# SCH_Addressable_through_hole_LEDs_2022-0.net
KiCad netlist of a schematic drawn in EasyEDA
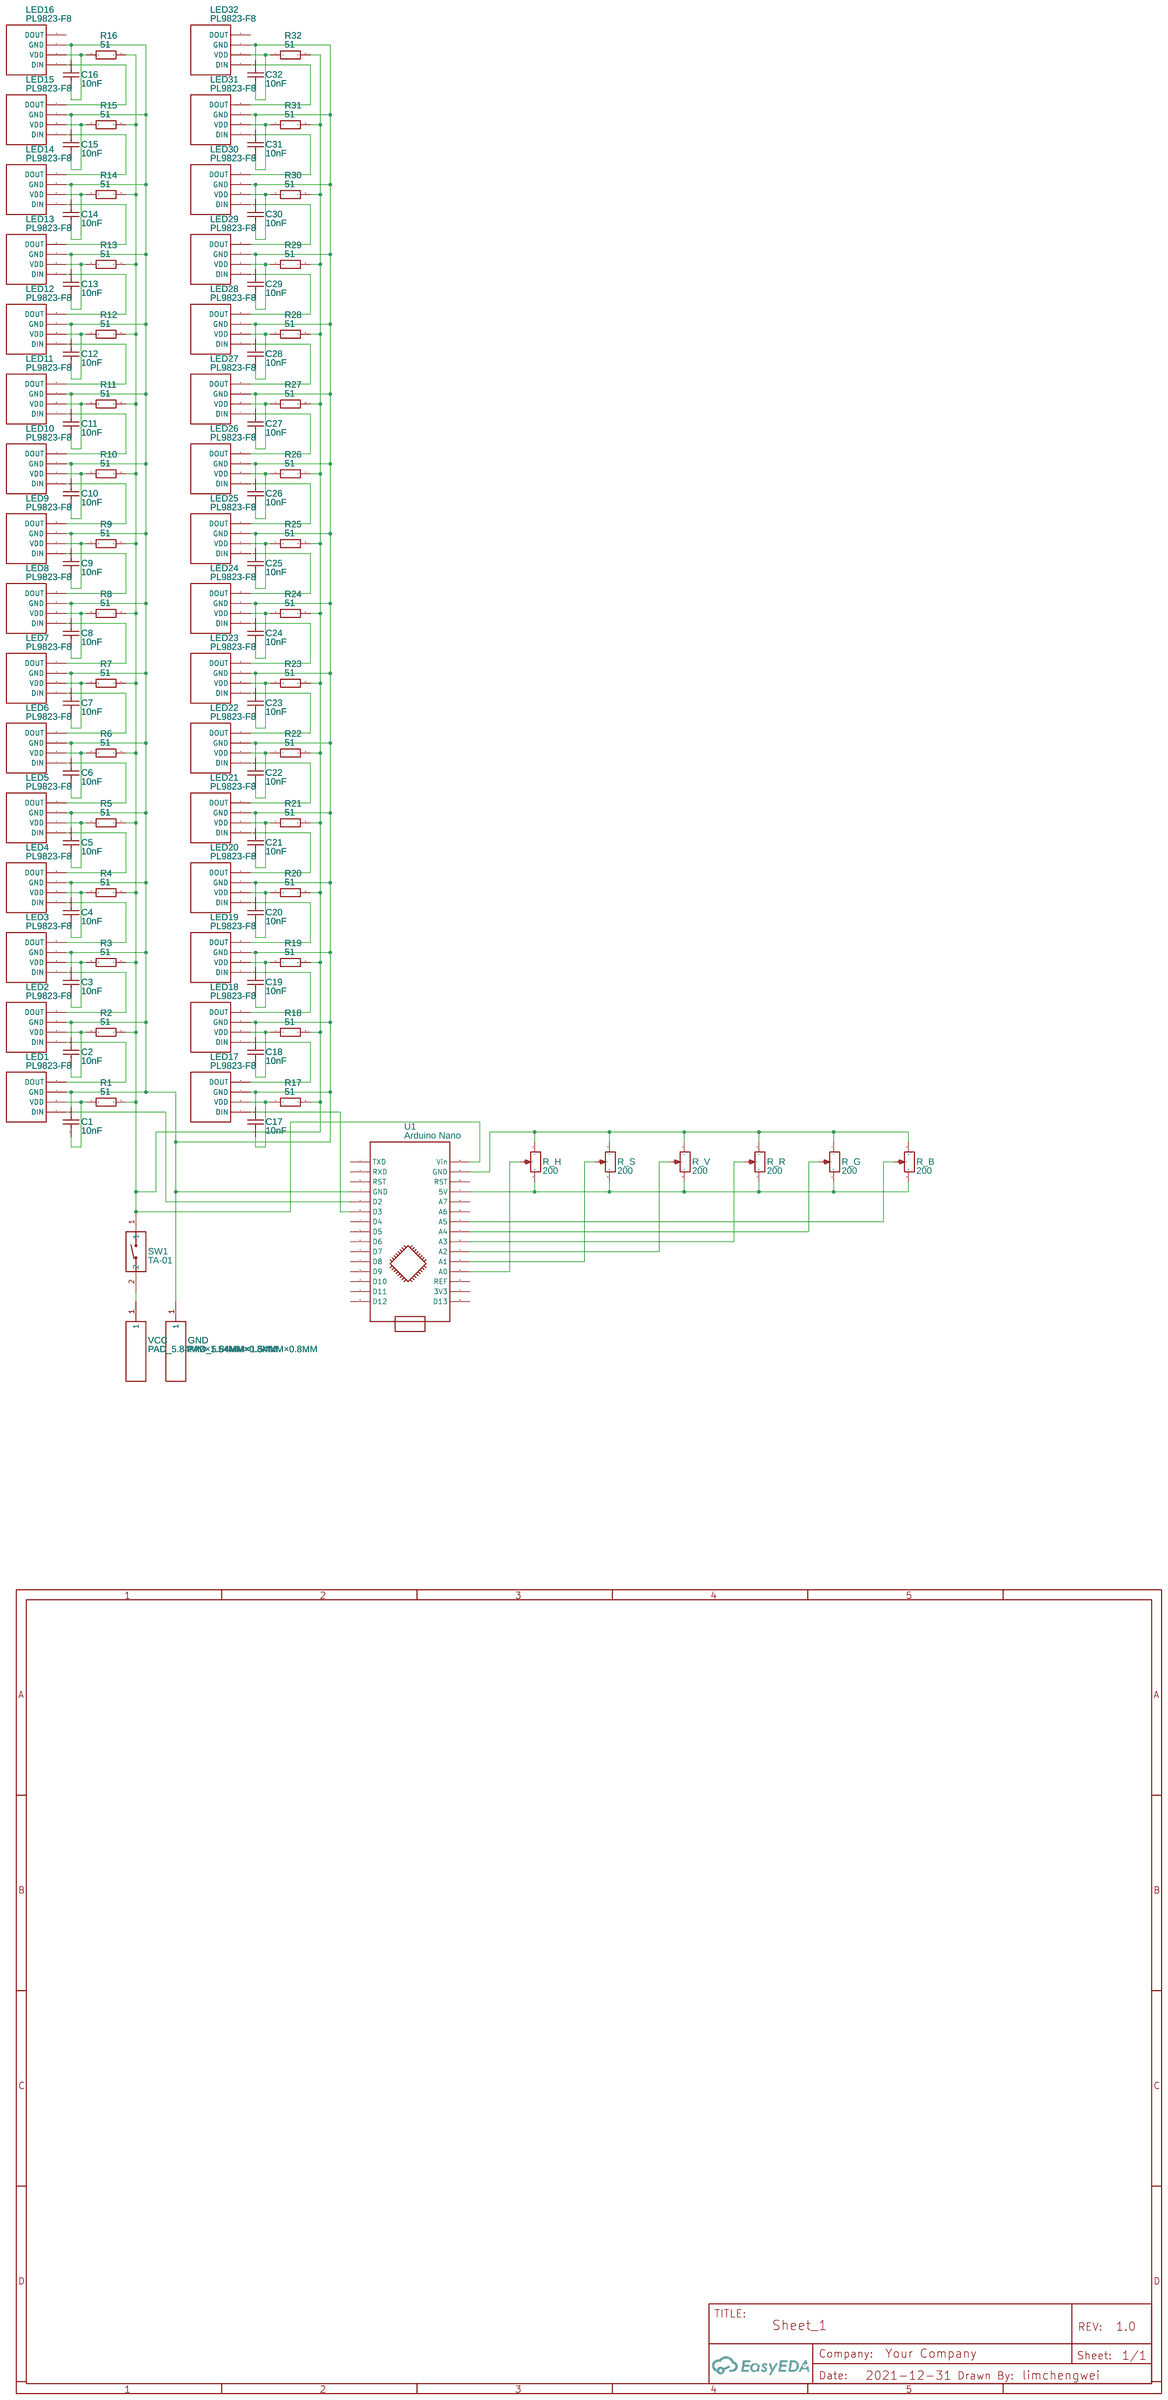
[diagram p0: schematic sheet]

(export (version "E")
  (design (tool "Eeschema 10.0.6"))
  (components
    (comp (ref "C1")
      (value "10nF")
      (fields
        (field (name "BOM_Manufacturer Part") "CC1H103ZC1FD3F4D10MF")
        (field (name "BOM_Supplier Part") "C254084")
      )
      (libsource (lib "") (part "CC1H103ZC1FD3F4D10MF"))
    )
    (comp (ref "C2")
      (value "10nF")
      (fields
        (field (name "BOM_Manufacturer Part") "CC1H103ZC1FD3F4D10MF")
        (field (name "BOM_Supplier Part") "C254084")
      )
      (libsource (lib "") (part "CC1H103ZC1FD3F4D10MF"))
    )
    (comp (ref "C3")
      (value "10nF")
      (fields
        (field (name "BOM_Manufacturer Part") "CC1H103ZC1FD3F4D10MF")
        (field (name "BOM_Supplier Part") "C254084")
      )
      (libsource (lib "") (part "CC1H103ZC1FD3F4D10MF"))
    )
    (comp (ref "C4")
      (value "10nF")
      (fields
        (field (name "BOM_Manufacturer Part") "CC1H103ZC1FD3F4D10MF")
        (field (name "BOM_Supplier Part") "C254084")
      )
      (libsource (lib "") (part "CC1H103ZC1FD3F4D10MF"))
    )
    (comp (ref "C5")
      (value "10nF")
      (fields
        (field (name "BOM_Manufacturer Part") "CC1H103ZC1FD3F4D10MF")
        (field (name "BOM_Supplier Part") "C254084")
      )
      (libsource (lib "") (part "CC1H103ZC1FD3F4D10MF"))
    )
    (comp (ref "C6")
      (value "10nF")
      (fields
        (field (name "BOM_Manufacturer Part") "CC1H103ZC1FD3F4D10MF")
        (field (name "BOM_Supplier Part") "C254084")
      )
      (libsource (lib "") (part "CC1H103ZC1FD3F4D10MF"))
    )
    (comp (ref "C7")
      (value "10nF")
      (fields
        (field (name "BOM_Manufacturer Part") "CC1H103ZC1FD3F4D10MF")
        (field (name "BOM_Supplier Part") "C254084")
      )
      (libsource (lib "") (part "CC1H103ZC1FD3F4D10MF"))
    )
    (comp (ref "C8")
      (value "10nF")
      (fields
        (field (name "BOM_Manufacturer Part") "CC1H103ZC1FD3F4D10MF")
        (field (name "BOM_Supplier Part") "C254084")
      )
      (libsource (lib "") (part "CC1H103ZC1FD3F4D10MF"))
    )
    (comp (ref "C9")
      (value "10nF")
      (fields
        (field (name "BOM_Manufacturer Part") "CC1H103ZC1FD3F4D10MF")
        (field (name "BOM_Supplier Part") "C254084")
      )
      (libsource (lib "") (part "CC1H103ZC1FD3F4D10MF"))
    )
    (comp (ref "C10")
      (value "10nF")
      (fields
        (field (name "BOM_Manufacturer Part") "CC1H103ZC1FD3F4D10MF")
        (field (name "BOM_Supplier Part") "C254084")
      )
      (libsource (lib "") (part "CC1H103ZC1FD3F4D10MF"))
    )
    (comp (ref "C11")
      (value "10nF")
      (fields
        (field (name "BOM_Manufacturer Part") "CC1H103ZC1FD3F4D10MF")
        (field (name "BOM_Supplier Part") "C254084")
      )
      (libsource (lib "") (part "CC1H103ZC1FD3F4D10MF"))
    )
    (comp (ref "C12")
      (value "10nF")
      (fields
        (field (name "BOM_Manufacturer Part") "CC1H103ZC1FD3F4D10MF")
        (field (name "BOM_Supplier Part") "C254084")
      )
      (libsource (lib "") (part "CC1H103ZC1FD3F4D10MF"))
    )
    (comp (ref "C13")
      (value "10nF")
      (fields
        (field (name "BOM_Manufacturer Part") "CC1H103ZC1FD3F4D10MF")
        (field (name "BOM_Supplier Part") "C254084")
      )
      (libsource (lib "") (part "CC1H103ZC1FD3F4D10MF"))
    )
    (comp (ref "C14")
      (value "10nF")
      (fields
        (field (name "BOM_Manufacturer Part") "CC1H103ZC1FD3F4D10MF")
        (field (name "BOM_Supplier Part") "C254084")
      )
      (libsource (lib "") (part "CC1H103ZC1FD3F4D10MF"))
    )
    (comp (ref "C15")
      (value "10nF")
      (fields
        (field (name "BOM_Manufacturer Part") "CC1H103ZC1FD3F4D10MF")
        (field (name "BOM_Supplier Part") "C254084")
      )
      (libsource (lib "") (part "CC1H103ZC1FD3F4D10MF"))
    )
    (comp (ref "C16")
      (value "10nF")
      (fields
        (field (name "BOM_Manufacturer Part") "CC1H103ZC1FD3F4D10MF")
        (field (name "BOM_Supplier Part") "C254084")
      )
      (libsource (lib "") (part "CC1H103ZC1FD3F4D10MF"))
    )
    (comp (ref "C17")
      (value "10nF")
      (fields
        (field (name "BOM_Manufacturer Part") "CC1H103ZC1FD3F4D10MF")
        (field (name "BOM_Supplier Part") "C254084")
      )
      (libsource (lib "") (part "CC1H103ZC1FD3F4D10MF"))
    )
    (comp (ref "C18")
      (value "10nF")
      (fields
        (field (name "BOM_Manufacturer Part") "CC1H103ZC1FD3F4D10MF")
        (field (name "BOM_Supplier Part") "C254084")
      )
      (libsource (lib "") (part "CC1H103ZC1FD3F4D10MF"))
    )
    (comp (ref "C19")
      (value "10nF")
      (fields
        (field (name "BOM_Manufacturer Part") "CC1H103ZC1FD3F4D10MF")
        (field (name "BOM_Supplier Part") "C254084")
      )
      (libsource (lib "") (part "CC1H103ZC1FD3F4D10MF"))
    )
    (comp (ref "C20")
      (value "10nF")
      (fields
        (field (name "BOM_Manufacturer Part") "CC1H103ZC1FD3F4D10MF")
        (field (name "BOM_Supplier Part") "C254084")
      )
      (libsource (lib "") (part "CC1H103ZC1FD3F4D10MF"))
    )
    (comp (ref "C21")
      (value "10nF")
      (fields
        (field (name "BOM_Manufacturer Part") "CC1H103ZC1FD3F4D10MF")
        (field (name "BOM_Supplier Part") "C254084")
      )
      (libsource (lib "") (part "CC1H103ZC1FD3F4D10MF"))
    )
    (comp (ref "C22")
      (value "10nF")
      (fields
        (field (name "BOM_Manufacturer Part") "CC1H103ZC1FD3F4D10MF")
        (field (name "BOM_Supplier Part") "C254084")
      )
      (libsource (lib "") (part "CC1H103ZC1FD3F4D10MF"))
    )
    (comp (ref "C23")
      (value "10nF")
      (fields
        (field (name "BOM_Manufacturer Part") "CC1H103ZC1FD3F4D10MF")
        (field (name "BOM_Supplier Part") "C254084")
      )
      (libsource (lib "") (part "CC1H103ZC1FD3F4D10MF"))
    )
    (comp (ref "C24")
      (value "10nF")
      (fields
        (field (name "BOM_Manufacturer Part") "CC1H103ZC1FD3F4D10MF")
        (field (name "BOM_Supplier Part") "C254084")
      )
      (libsource (lib "") (part "CC1H103ZC1FD3F4D10MF"))
    )
    (comp (ref "C25")
      (value "10nF")
      (fields
        (field (name "BOM_Manufacturer Part") "CC1H103ZC1FD3F4D10MF")
        (field (name "BOM_Supplier Part") "C254084")
      )
      (libsource (lib "") (part "CC1H103ZC1FD3F4D10MF"))
    )
    (comp (ref "C26")
      (value "10nF")
      (fields
        (field (name "BOM_Manufacturer Part") "CC1H103ZC1FD3F4D10MF")
        (field (name "BOM_Supplier Part") "C254084")
      )
      (libsource (lib "") (part "CC1H103ZC1FD3F4D10MF"))
    )
    (comp (ref "C27")
      (value "10nF")
      (fields
        (field (name "BOM_Manufacturer Part") "CC1H103ZC1FD3F4D10MF")
        (field (name "BOM_Supplier Part") "C254084")
      )
      (libsource (lib "") (part "CC1H103ZC1FD3F4D10MF"))
    )
    (comp (ref "C28")
      (value "10nF")
      (fields
        (field (name "BOM_Manufacturer Part") "CC1H103ZC1FD3F4D10MF")
        (field (name "BOM_Supplier Part") "C254084")
      )
      (libsource (lib "") (part "CC1H103ZC1FD3F4D10MF"))
    )
    (comp (ref "C29")
      (value "10nF")
      (fields
        (field (name "BOM_Manufacturer Part") "CC1H103ZC1FD3F4D10MF")
        (field (name "BOM_Supplier Part") "C254084")
      )
      (libsource (lib "") (part "CC1H103ZC1FD3F4D10MF"))
    )
    (comp (ref "C30")
      (value "10nF")
      (fields
        (field (name "BOM_Manufacturer Part") "CC1H103ZC1FD3F4D10MF")
        (field (name "BOM_Supplier Part") "C254084")
      )
      (libsource (lib "") (part "CC1H103ZC1FD3F4D10MF"))
    )
    (comp (ref "C31")
      (value "10nF")
      (fields
        (field (name "BOM_Manufacturer Part") "CC1H103ZC1FD3F4D10MF")
        (field (name "BOM_Supplier Part") "C254084")
      )
      (libsource (lib "") (part "CC1H103ZC1FD3F4D10MF"))
    )
    (comp (ref "C32")
      (value "10nF")
      (fields
        (field (name "BOM_Manufacturer Part") "CC1H103ZC1FD3F4D10MF")
        (field (name "BOM_Supplier Part") "C254084")
      )
      (libsource (lib "") (part "CC1H103ZC1FD3F4D10MF"))
    )
    (comp (ref "GND")
      (value "PAD_5.84MM×1.54MM×0.8MM")
      (fields
        (field (name "BOM_Manufacturer Part") "PAD_5.84mm×1.54mm×0.8mm")
        (field (name "BOM_Supplier Part") "C9900000335")
      )
      (libsource (lib "") (part "PAD_5.84MM×1.54MM×0.8MM"))
    )
    (comp (ref "LED1")
      (value "PL9823-F8")
      (fields (field (name "BOM_Manufacturer Part") "PL9823"))
      (libsource (lib "") (part "PL9823-F8"))
    )
    (comp (ref "LED2")
      (value "PL9823-F8")
      (fields (field (name "BOM_Manufacturer Part") "PL9823"))
      (libsource (lib "") (part "PL9823-F8"))
    )
    (comp (ref "LED3")
      (value "PL9823-F8")
      (fields (field (name "BOM_Manufacturer Part") "PL9823"))
      (libsource (lib "") (part "PL9823-F8"))
    )
    (comp (ref "LED4")
      (value "PL9823-F8")
      (fields (field (name "BOM_Manufacturer Part") "PL9823"))
      (libsource (lib "") (part "PL9823-F8"))
    )
    (comp (ref "LED5")
      (value "PL9823-F8")
      (fields (field (name "BOM_Manufacturer Part") "PL9823"))
      (libsource (lib "") (part "PL9823-F8"))
    )
    (comp (ref "LED6")
      (value "PL9823-F8")
      (fields (field (name "BOM_Manufacturer Part") "PL9823"))
      (libsource (lib "") (part "PL9823-F8"))
    )
    (comp (ref "LED7")
      (value "PL9823-F8")
      (fields (field (name "BOM_Manufacturer Part") "PL9823"))
      (libsource (lib "") (part "PL9823-F8"))
    )
    (comp (ref "LED8")
      (value "PL9823-F8")
      (fields (field (name "BOM_Manufacturer Part") "PL9823"))
      (libsource (lib "") (part "PL9823-F8"))
    )
    (comp (ref "LED9")
      (value "PL9823-F8")
      (fields (field (name "BOM_Manufacturer Part") "PL9823"))
      (libsource (lib "") (part "PL9823-F8"))
    )
    (comp (ref "LED10")
      (value "PL9823-F8")
      (fields (field (name "BOM_Manufacturer Part") "PL9823"))
      (libsource (lib "") (part "PL9823-F8"))
    )
    (comp (ref "LED11")
      (value "PL9823-F8")
      (fields (field (name "BOM_Manufacturer Part") "PL9823"))
      (libsource (lib "") (part "PL9823-F8"))
    )
    (comp (ref "LED12")
      (value "PL9823-F8")
      (fields (field (name "BOM_Manufacturer Part") "PL9823"))
      (libsource (lib "") (part "PL9823-F8"))
    )
    (comp (ref "LED13")
      (value "PL9823-F8")
      (fields (field (name "BOM_Manufacturer Part") "PL9823"))
      (libsource (lib "") (part "PL9823-F8"))
    )
    (comp (ref "LED14")
      (value "PL9823-F8")
      (fields (field (name "BOM_Manufacturer Part") "PL9823"))
      (libsource (lib "") (part "PL9823-F8"))
    )
    (comp (ref "LED15")
      (value "PL9823-F8")
      (fields (field (name "BOM_Manufacturer Part") "PL9823"))
      (libsource (lib "") (part "PL9823-F8"))
    )
    (comp (ref "LED16")
      (value "PL9823-F8")
      (fields (field (name "BOM_Manufacturer Part") "PL9823"))
      (libsource (lib "") (part "PL9823-F8"))
    )
    (comp (ref "LED17")
      (value "PL9823-F8")
      (fields (field (name "BOM_Manufacturer Part") "PL9823"))
      (libsource (lib "") (part "PL9823-F8"))
    )
    (comp (ref "LED18")
      (value "PL9823-F8")
      (fields (field (name "BOM_Manufacturer Part") "PL9823"))
      (libsource (lib "") (part "PL9823-F8"))
    )
    (comp (ref "LED19")
      (value "PL9823-F8")
      (fields (field (name "BOM_Manufacturer Part") "PL9823"))
      (libsource (lib "") (part "PL9823-F8"))
    )
    (comp (ref "LED20")
      (value "PL9823-F8")
      (fields (field (name "BOM_Manufacturer Part") "PL9823"))
      (libsource (lib "") (part "PL9823-F8"))
    )
    (comp (ref "LED21")
      (value "PL9823-F8")
      (fields (field (name "BOM_Manufacturer Part") "PL9823"))
      (libsource (lib "") (part "PL9823-F8"))
    )
    (comp (ref "LED22")
      (value "PL9823-F8")
      (fields (field (name "BOM_Manufacturer Part") "PL9823"))
      (libsource (lib "") (part "PL9823-F8"))
    )
    (comp (ref "LED23")
      (value "PL9823-F8")
      (fields (field (name "BOM_Manufacturer Part") "PL9823"))
      (libsource (lib "") (part "PL9823-F8"))
    )
    (comp (ref "LED24")
      (value "PL9823-F8")
      (fields (field (name "BOM_Manufacturer Part") "PL9823"))
      (libsource (lib "") (part "PL9823-F8"))
    )
    (comp (ref "LED25")
      (value "PL9823-F8")
      (fields (field (name "BOM_Manufacturer Part") "PL9823"))
      (libsource (lib "") (part "PL9823-F8"))
    )
    (comp (ref "LED26")
      (value "PL9823-F8")
      (fields (field (name "BOM_Manufacturer Part") "PL9823"))
      (libsource (lib "") (part "PL9823-F8"))
    )
    (comp (ref "LED27")
      (value "PL9823-F8")
      (fields (field (name "BOM_Manufacturer Part") "PL9823"))
      (libsource (lib "") (part "PL9823-F8"))
    )
    (comp (ref "LED28")
      (value "PL9823-F8")
      (fields (field (name "BOM_Manufacturer Part") "PL9823"))
      (libsource (lib "") (part "PL9823-F8"))
    )
    (comp (ref "LED29")
      (value "PL9823-F8")
      (fields (field (name "BOM_Manufacturer Part") "PL9823"))
      (libsource (lib "") (part "PL9823-F8"))
    )
    (comp (ref "LED30")
      (value "PL9823-F8")
      (fields (field (name "BOM_Manufacturer Part") "PL9823"))
      (libsource (lib "") (part "PL9823-F8"))
    )
    (comp (ref "LED31")
      (value "PL9823-F8")
      (fields (field (name "BOM_Manufacturer Part") "PL9823"))
      (libsource (lib "") (part "PL9823-F8"))
    )
    (comp (ref "LED32")
      (value "PL9823-F8")
      (fields (field (name "BOM_Manufacturer Part") "PL9823"))
      (libsource (lib "") (part "PL9823-F8"))
    )
    (comp (ref "R1")
      (value "51")
      (fields (field (name "BOM_Supplier Part") "C119319"))
      (libsource (lib "") (part "MF1/4W-620Ω±1% T52"))
    )
    (comp (ref "R2")
      (value "51")
      (fields (field (name "BOM_Supplier Part") "C119319"))
      (libsource (lib "") (part "MF1/4W-620Ω±1% T52"))
    )
    (comp (ref "R3")
      (value "51")
      (fields (field (name "BOM_Supplier Part") "C119319"))
      (libsource (lib "") (part "MF1/4W-620Ω±1% T52"))
    )
    (comp (ref "R4")
      (value "51")
      (fields (field (name "BOM_Supplier Part") "C119319"))
      (libsource (lib "") (part "MF1/4W-620Ω±1% T52"))
    )
    (comp (ref "R5")
      (value "51")
      (fields (field (name "BOM_Supplier Part") "C119319"))
      (libsource (lib "") (part "MF1/4W-620Ω±1% T52"))
    )
    (comp (ref "R6")
      (value "51")
      (fields (field (name "BOM_Supplier Part") "C119319"))
      (libsource (lib "") (part "MF1/4W-620Ω±1% T52"))
    )
    (comp (ref "R7")
      (value "51")
      (fields (field (name "BOM_Supplier Part") "C119319"))
      (libsource (lib "") (part "MF1/4W-620Ω±1% T52"))
    )
    (comp (ref "R8")
      (value "51")
      (fields (field (name "BOM_Supplier Part") "C119319"))
      (libsource (lib "") (part "MF1/4W-620Ω±1% T52"))
    )
    (comp (ref "R9")
      (value "51")
      (fields (field (name "BOM_Supplier Part") "C119319"))
      (libsource (lib "") (part "MF1/4W-620Ω±1% T52"))
    )
    (comp (ref "R10")
      (value "51")
      (fields (field (name "BOM_Supplier Part") "C119319"))
      (libsource (lib "") (part "MF1/4W-620Ω±1% T52"))
    )
    (comp (ref "R11")
      (value "51")
      (fields (field (name "BOM_Supplier Part") "C119319"))
      (libsource (lib "") (part "MF1/4W-620Ω±1% T52"))
    )
    (comp (ref "R12")
      (value "51")
      (fields (field (name "BOM_Supplier Part") "C119319"))
      (libsource (lib "") (part "MF1/4W-620Ω±1% T52"))
    )
    (comp (ref "R13")
      (value "51")
      (fields (field (name "BOM_Supplier Part") "C119319"))
      (libsource (lib "") (part "MF1/4W-620Ω±1% T52"))
    )
    (comp (ref "R14")
      (value "51")
      (fields (field (name "BOM_Supplier Part") "C119319"))
      (libsource (lib "") (part "MF1/4W-620Ω±1% T52"))
    )
    (comp (ref "R15")
      (value "51")
      (fields (field (name "BOM_Supplier Part") "C119319"))
      (libsource (lib "") (part "MF1/4W-620Ω±1% T52"))
    )
    (comp (ref "R16")
      (value "51")
      (fields (field (name "BOM_Supplier Part") "C119319"))
      (libsource (lib "") (part "MF1/4W-620Ω±1% T52"))
    )
    (comp (ref "R17")
      (value "51")
      (fields (field (name "BOM_Supplier Part") "C119319"))
      (libsource (lib "") (part "MF1/4W-620Ω±1% T52"))
    )
    (comp (ref "R18")
      (value "51")
      (fields (field (name "BOM_Supplier Part") "C119319"))
      (libsource (lib "") (part "MF1/4W-620Ω±1% T52"))
    )
    (comp (ref "R19")
      (value "51")
      (fields (field (name "BOM_Supplier Part") "C119319"))
      (libsource (lib "") (part "MF1/4W-620Ω±1% T52"))
    )
    (comp (ref "R20")
      (value "51")
      (fields (field (name "BOM_Supplier Part") "C119319"))
      (libsource (lib "") (part "MF1/4W-620Ω±1% T52"))
    )
    (comp (ref "R21")
      (value "51")
      (fields (field (name "BOM_Supplier Part") "C119319"))
      (libsource (lib "") (part "MF1/4W-620Ω±1% T52"))
    )
    (comp (ref "R22")
      (value "51")
      (fields (field (name "BOM_Supplier Part") "C119319"))
      (libsource (lib "") (part "MF1/4W-620Ω±1% T52"))
    )
    (comp (ref "R23")
      (value "51")
      (fields (field (name "BOM_Supplier Part") "C119319"))
      (libsource (lib "") (part "MF1/4W-620Ω±1% T52"))
    )
    (comp (ref "R24")
      (value "51")
      (fields (field (name "BOM_Supplier Part") "C119319"))
      (libsource (lib "") (part "MF1/4W-620Ω±1% T52"))
    )
    (comp (ref "R25")
      (value "51")
      (fields (field (name "BOM_Supplier Part") "C119319"))
      (libsource (lib "") (part "MF1/4W-620Ω±1% T52"))
    )
    (comp (ref "R26")
      (value "51")
      (fields (field (name "BOM_Supplier Part") "C119319"))
      (libsource (lib "") (part "MF1/4W-620Ω±1% T52"))
    )
    (comp (ref "R27")
      (value "51")
      (fields (field (name "BOM_Supplier Part") "C119319"))
      (libsource (lib "") (part "MF1/4W-620Ω±1% T52"))
    )
    (comp (ref "R28")
      (value "51")
      (fields (field (name "BOM_Supplier Part") "C119319"))
      (libsource (lib "") (part "MF1/4W-620Ω±1% T52"))
    )
    (comp (ref "R29")
      (value "51")
      (fields (field (name "BOM_Supplier Part") "C119319"))
      (libsource (lib "") (part "MF1/4W-620Ω±1% T52"))
    )
    (comp (ref "R30")
      (value "51")
      (fields (field (name "BOM_Supplier Part") "C119319"))
      (libsource (lib "") (part "MF1/4W-620Ω±1% T52"))
    )
    (comp (ref "R31")
      (value "51")
      (fields (field (name "BOM_Supplier Part") "C119319"))
      (libsource (lib "") (part "MF1/4W-620Ω±1% T52"))
    )
    (comp (ref "R32")
      (value "51")
      (fields (field (name "BOM_Supplier Part") "C119319"))
      (libsource (lib "") (part "MF1/4W-620Ω±1% T52"))
    )
    (comp (ref "R_B")
      (value "200")
      (fields
        (field (name "BOM_Manufacturer Part") "3362P-1-201LF")
        (field (name "BOM_Supplier Part") "C124581")
      )
      (libsource (lib "") (part "3362P-1-201LF_4"))
    )
    (comp (ref "R_G")
      (value "200")
      (fields
        (field (name "BOM_Manufacturer Part") "3362P-1-201LF")
        (field (name "BOM_Supplier Part") "C124581")
      )
      (libsource (lib "") (part "3362P-1-201LF_5"))
    )
    (comp (ref "R_H")
      (value "200")
      (fields
        (field (name "BOM_Manufacturer Part") "3362P-1-201LF")
        (field (name "BOM_Supplier Part") "C124581")
      )
      (libsource (lib "") (part "3362P-1-201LF_1"))
    )
    (comp (ref "R_R")
      (value "200")
      (fields
        (field (name "BOM_Manufacturer Part") "3362P-1-201LF")
        (field (name "BOM_Supplier Part") "C124581")
      )
      (libsource (lib "") (part "3362P-1-201LF"))
    )
    (comp (ref "R_S")
      (value "200")
      (fields
        (field (name "BOM_Manufacturer Part") "3362P-1-201LF")
        (field (name "BOM_Supplier Part") "C124581")
      )
      (libsource (lib "") (part "3362P-1-201LF_3"))
    )
    (comp (ref "R_V")
      (value "200")
      (fields
        (field (name "BOM_Manufacturer Part") "3362P-1-201LF")
        (field (name "BOM_Supplier Part") "C124581")
      )
      (libsource (lib "") (part "3362P-1-201LF_2"))
    )
    (comp (ref "SW1")
      (value "TA-01")
      (fields (field (name "BOM_Supplier Part") "C559136"))
      (libsource (lib "") (part "TA-01"))
    )
    (comp (ref "U1") (value "Arduino Nano") (libsource (lib "") (part "Arduino Nano")))
    (comp (ref "VCC")
      (value "PAD_5.84MM×1.54MM×0.8MM")
      (fields
        (field (name "BOM_Manufacturer Part") "PAD_5.84mm×1.54mm×0.8mm")
        (field (name "BOM_Supplier Part") "C9900000335")
      )
      (libsource (lib "") (part "PAD_5.84MM×1.54MM×0.8MM_1"))
    )
  )
  (nets
    (net (code "1") (name "Net-(LED1-DIN)") (class "Default")
      (node (ref "LED1") (pin "4") (pinfunction "DIN_4") (pintype "unspecified"))
      (node (ref "U1") (pin "5") (pinfunction "D2_5") (pintype "unspecified"))
    )
    (net (code "2") (name "Net-(LED1-DOUT)") (class "Default")
      (node (ref "LED1") (pin "2") (pinfunction "DOUT_2") (pintype "unspecified"))
      (node (ref "LED2") (pin "4") (pinfunction "DIN_4") (pintype "unspecified"))
    )
    (net (code "3") (name "Net-(LED1-GND)") (class "Default")
      (node (ref "C1") (pin "2") (pinfunction "2_2") (pintype "input"))
      (node (ref "C10") (pin "2") (pinfunction "2_2") (pintype "input"))
      (node (ref "C11") (pin "2") (pinfunction "2_2") (pintype "input"))
      (node (ref "C12") (pin "2") (pinfunction "2_2") (pintype "input"))
      (node (ref "C13") (pin "2") (pinfunction "2_2") (pintype "input"))
      (node (ref "C14") (pin "2") (pinfunction "2_2") (pintype "input"))
      (node (ref "C15") (pin "2") (pinfunction "2_2") (pintype "input"))
      (node (ref "C16") (pin "2") (pinfunction "2_2") (pintype "input"))
      (node (ref "C17") (pin "2") (pinfunction "2_2") (pintype "input"))
      (node (ref "C18") (pin "2") (pinfunction "2_2") (pintype "input"))
      (node (ref "C19") (pin "2") (pinfunction "2_2") (pintype "input"))
      (node (ref "C2") (pin "2") (pinfunction "2_2") (pintype "input"))
      (node (ref "C20") (pin "2") (pinfunction "2_2") (pintype "input"))
      (node (ref "C21") (pin "2") (pinfunction "2_2") (pintype "input"))
      (node (ref "C22") (pin "2") (pinfunction "2_2") (pintype "input"))
      (node (ref "C23") (pin "2") (pinfunction "2_2") (pintype "input"))
      (node (ref "C24") (pin "2") (pinfunction "2_2") (pintype "input"))
      (node (ref "C25") (pin "2") (pinfunction "2_2") (pintype "input"))
      (node (ref "C26") (pin "2") (pinfunction "2_2") (pintype "input"))
      (node (ref "C27") (pin "2") (pinfunction "2_2") (pintype "input"))
      (node (ref "C28") (pin "2") (pinfunction "2_2") (pintype "input"))
      (node (ref "C29") (pin "2") (pinfunction "2_2") (pintype "input"))
      (node (ref "C3") (pin "2") (pinfunction "2_2") (pintype "input"))
      (node (ref "C30") (pin "2") (pinfunction "2_2") (pintype "input"))
      (node (ref "C31") (pin "2") (pinfunction "2_2") (pintype "input"))
      (node (ref "C32") (pin "2") (pinfunction "2_2") (pintype "input"))
      (node (ref "C4") (pin "2") (pinfunction "2_2") (pintype "input"))
      (node (ref "C5") (pin "2") (pinfunction "2_2") (pintype "input"))
      (node (ref "C6") (pin "2") (pinfunction "2_2") (pintype "input"))
      (node (ref "C7") (pin "2") (pinfunction "2_2") (pintype "input"))
      (node (ref "C8") (pin "2") (pinfunction "2_2") (pintype "input"))
      (node (ref "C9") (pin "2") (pinfunction "2_2") (pintype "input"))
      (node (ref "GND") (pin "1") (pinfunction "1_1") (pintype "unspecified"))
      (node (ref "LED1") (pin "1") (pinfunction "GND_1") (pintype "unspecified"))
      (node (ref "LED10") (pin "1") (pinfunction "GND_1") (pintype "unspecified"))
      (node (ref "LED11") (pin "1") (pinfunction "GND_1") (pintype "unspecified"))
      (node (ref "LED12") (pin "1") (pinfunction "GND_1") (pintype "unspecified"))
      (node (ref "LED13") (pin "1") (pinfunction "GND_1") (pintype "unspecified"))
      (node (ref "LED14") (pin "1") (pinfunction "GND_1") (pintype "unspecified"))
      (node (ref "LED15") (pin "1") (pinfunction "GND_1") (pintype "unspecified"))
      (node (ref "LED16") (pin "1") (pinfunction "GND_1") (pintype "unspecified"))
      (node (ref "LED17") (pin "1") (pinfunction "GND_1") (pintype "unspecified"))
      (node (ref "LED18") (pin "1") (pinfunction "GND_1") (pintype "unspecified"))
      (node (ref "LED19") (pin "1") (pinfunction "GND_1") (pintype "unspecified"))
      (node (ref "LED2") (pin "1") (pinfunction "GND_1") (pintype "unspecified"))
      (node (ref "LED20") (pin "1") (pinfunction "GND_1") (pintype "unspecified"))
      (node (ref "LED21") (pin "1") (pinfunction "GND_1") (pintype "unspecified"))
      (node (ref "LED22") (pin "1") (pinfunction "GND_1") (pintype "unspecified"))
      (node (ref "LED23") (pin "1") (pinfunction "GND_1") (pintype "unspecified"))
      (node (ref "LED24") (pin "1") (pinfunction "GND_1") (pintype "unspecified"))
      (node (ref "LED25") (pin "1") (pinfunction "GND_1") (pintype "unspecified"))
      (node (ref "LED26") (pin "1") (pinfunction "GND_1") (pintype "unspecified"))
      (node (ref "LED27") (pin "1") (pinfunction "GND_1") (pintype "unspecified"))
      (node (ref "LED28") (pin "1") (pinfunction "GND_1") (pintype "unspecified"))
      (node (ref "LED29") (pin "1") (pinfunction "GND_1") (pintype "unspecified"))
      (node (ref "LED3") (pin "1") (pinfunction "GND_1") (pintype "unspecified"))
      (node (ref "LED30") (pin "1") (pinfunction "GND_1") (pintype "unspecified"))
      (node (ref "LED31") (pin "1") (pinfunction "GND_1") (pintype "unspecified"))
      (node (ref "LED32") (pin "1") (pinfunction "GND_1") (pintype "unspecified"))
      (node (ref "LED4") (pin "1") (pinfunction "GND_1") (pintype "unspecified"))
      (node (ref "LED5") (pin "1") (pinfunction "GND_1") (pintype "unspecified"))
      (node (ref "LED6") (pin "1") (pinfunction "GND_1") (pintype "unspecified"))
      (node (ref "LED7") (pin "1") (pinfunction "GND_1") (pintype "unspecified"))
      (node (ref "LED8") (pin "1") (pinfunction "GND_1") (pintype "unspecified"))
      (node (ref "LED9") (pin "1") (pinfunction "GND_1") (pintype "unspecified"))
      (node (ref "U1") (pin "4") (pinfunction "GND_4") (pintype "unspecified"))
    )
    (net (code "4") (name "Net-(LED1-VDD)") (class "Default")
      (node (ref "C1") (pin "1") (pinfunction "1_1") (pintype "input"))
      (node (ref "LED1") (pin "3") (pinfunction "VDD_3") (pintype "unspecified"))
      (node (ref "R1") (pin "1") (pinfunction "1_1") (pintype "unspecified"))
    )
    (net (code "5") (name "Net-(LED2-DOUT)") (class "Default")
      (node (ref "LED2") (pin "2") (pinfunction "DOUT_2") (pintype "unspecified"))
      (node (ref "LED3") (pin "4") (pinfunction "DIN_4") (pintype "unspecified"))
    )
    (net (code "6") (name "Net-(LED2-VDD)") (class "Default")
      (node (ref "C2") (pin "1") (pinfunction "1_1") (pintype "input"))
      (node (ref "LED2") (pin "3") (pinfunction "VDD_3") (pintype "unspecified"))
      (node (ref "R2") (pin "1") (pinfunction "1_1") (pintype "unspecified"))
    )
    (net (code "7") (name "Net-(LED3-DOUT)") (class "Default")
      (node (ref "LED3") (pin "2") (pinfunction "DOUT_2") (pintype "unspecified"))
      (node (ref "LED4") (pin "4") (pinfunction "DIN_4") (pintype "unspecified"))
    )
    (net (code "8") (name "Net-(LED3-VDD)") (class "Default")
      (node (ref "C3") (pin "1") (pinfunction "1_1") (pintype "input"))
      (node (ref "LED3") (pin "3") (pinfunction "VDD_3") (pintype "unspecified"))
      (node (ref "R3") (pin "1") (pinfunction "1_1") (pintype "unspecified"))
    )
    (net (code "9") (name "Net-(LED4-DOUT)") (class "Default")
      (node (ref "LED4") (pin "2") (pinfunction "DOUT_2") (pintype "unspecified"))
      (node (ref "LED5") (pin "4") (pinfunction "DIN_4") (pintype "unspecified"))
    )
    (net (code "10") (name "Net-(LED4-VDD)") (class "Default")
      (node (ref "C4") (pin "1") (pinfunction "1_1") (pintype "input"))
      (node (ref "LED4") (pin "3") (pinfunction "VDD_3") (pintype "unspecified"))
      (node (ref "R4") (pin "1") (pinfunction "1_1") (pintype "unspecified"))
    )
    (net (code "11") (name "Net-(LED5-DOUT)") (class "Default")
      (node (ref "LED5") (pin "2") (pinfunction "DOUT_2") (pintype "unspecified"))
      (node (ref "LED6") (pin "4") (pinfunction "DIN_4") (pintype "unspecified"))
    )
    (net (code "12") (name "Net-(LED5-VDD)") (class "Default")
      (node (ref "C5") (pin "1") (pinfunction "1_1") (pintype "input"))
      (node (ref "LED5") (pin "3") (pinfunction "VDD_3") (pintype "unspecified"))
      (node (ref "R5") (pin "1") (pinfunction "1_1") (pintype "unspecified"))
    )
    (net (code "13") (name "Net-(LED6-DOUT)") (class "Default")
      (node (ref "LED6") (pin "2") (pinfunction "DOUT_2") (pintype "unspecified"))
      (node (ref "LED7") (pin "4") (pinfunction "DIN_4") (pintype "unspecified"))
    )
    (net (code "14") (name "Net-(LED6-VDD)") (class "Default")
      (node (ref "C6") (pin "1") (pinfunction "1_1") (pintype "input"))
      (node (ref "LED6") (pin "3") (pinfunction "VDD_3") (pintype "unspecified"))
      (node (ref "R6") (pin "1") (pinfunction "1_1") (pintype "unspecified"))
    )
    (net (code "15") (name "Net-(LED7-DOUT)") (class "Default")
      (node (ref "LED7") (pin "2") (pinfunction "DOUT_2") (pintype "unspecified"))
      (node (ref "LED8") (pin "4") (pinfunction "DIN_4") (pintype "unspecified"))
    )
    (net (code "16") (name "Net-(LED7-VDD)") (class "Default")
      (node (ref "C7") (pin "1") (pinfunction "1_1") (pintype "input"))
      (node (ref "LED7") (pin "3") (pinfunction "VDD_3") (pintype "unspecified"))
      (node (ref "R7") (pin "1") (pinfunction "1_1") (pintype "unspecified"))
    )
    (net (code "17") (name "Net-(LED8-DOUT)") (class "Default")
      (node (ref "LED8") (pin "2") (pinfunction "DOUT_2") (pintype "unspecified"))
      (node (ref "LED9") (pin "4") (pinfunction "DIN_4") (pintype "unspecified"))
    )
    (net (code "18") (name "Net-(LED8-VDD)") (class "Default")
      (node (ref "C8") (pin "1") (pinfunction "1_1") (pintype "input"))
      (node (ref "LED8") (pin "3") (pinfunction "VDD_3") (pintype "unspecified"))
      (node (ref "R8") (pin "1") (pinfunction "1_1") (pintype "unspecified"))
    )
    (net (code "19") (name "Net-(LED9-VDD)") (class "Default")
      (node (ref "C9") (pin "1") (pinfunction "1_1") (pintype "input"))
      (node (ref "LED9") (pin "3") (pinfunction "VDD_3") (pintype "unspecified"))
      (node (ref "R9") (pin "1") (pinfunction "1_1") (pintype "unspecified"))
    )
    (net (code "20") (name "Net-(LED10-DIN)") (class "Default")
      (node (ref "LED10") (pin "4") (pinfunction "DIN_4") (pintype "unspecified"))
      (node (ref "LED9") (pin "2") (pinfunction "DOUT_2") (pintype "unspecified"))
    )
    (net (code "21") (name "Net-(LED10-DOUT)") (class "Default")
      (node (ref "LED10") (pin "2") (pinfunction "DOUT_2") (pintype "unspecified"))
      (node (ref "LED11") (pin "4") (pinfunction "DIN_4") (pintype "unspecified"))
    )
    (net (code "22") (name "Net-(LED10-VDD)") (class "Default")
      (node (ref "C10") (pin "1") (pinfunction "1_1") (pintype "input"))
      (node (ref "LED10") (pin "3") (pinfunction "VDD_3") (pintype "unspecified"))
      (node (ref "R10") (pin "1") (pinfunction "1_1") (pintype "unspecified"))
    )
    (net (code "23") (name "Net-(LED11-DOUT)") (class "Default")
      (node (ref "LED11") (pin "2") (pinfunction "DOUT_2") (pintype "unspecified"))
      (node (ref "LED12") (pin "4") (pinfunction "DIN_4") (pintype "unspecified"))
    )
    (net (code "24") (name "Net-(LED11-VDD)") (class "Default")
      (node (ref "C11") (pin "1") (pinfunction "1_1") (pintype "input"))
      (node (ref "LED11") (pin "3") (pinfunction "VDD_3") (pintype "unspecified"))
      (node (ref "R11") (pin "1") (pinfunction "1_1") (pintype "unspecified"))
    )
    (net (code "25") (name "Net-(LED12-DOUT)") (class "Default")
      (node (ref "LED12") (pin "2") (pinfunction "DOUT_2") (pintype "unspecified"))
      (node (ref "LED13") (pin "4") (pinfunction "DIN_4") (pintype "unspecified"))
    )
    (net (code "26") (name "Net-(LED12-VDD)") (class "Default")
      (node (ref "C12") (pin "1") (pinfunction "1_1") (pintype "input"))
      (node (ref "LED12") (pin "3") (pinfunction "VDD_3") (pintype "unspecified"))
      (node (ref "R12") (pin "1") (pinfunction "1_1") (pintype "unspecified"))
    )
    (net (code "27") (name "Net-(LED13-DOUT)") (class "Default")
      (node (ref "LED13") (pin "2") (pinfunction "DOUT_2") (pintype "unspecified"))
      (node (ref "LED14") (pin "4") (pinfunction "DIN_4") (pintype "unspecified"))
    )
    (net (code "28") (name "Net-(LED13-VDD)") (class "Default")
      (node (ref "C13") (pin "1") (pinfunction "1_1") (pintype "input"))
      (node (ref "LED13") (pin "3") (pinfunction "VDD_3") (pintype "unspecified"))
      (node (ref "R13") (pin "1") (pinfunction "1_1") (pintype "unspecified"))
    )
    (net (code "29") (name "Net-(LED14-DOUT)") (class "Default")
      (node (ref "LED14") (pin "2") (pinfunction "DOUT_2") (pintype "unspecified"))
      (node (ref "LED15") (pin "4") (pinfunction "DIN_4") (pintype "unspecified"))
    )
    (net (code "30") (name "Net-(LED14-VDD)") (class "Default")
      (node (ref "C14") (pin "1") (pinfunction "1_1") (pintype "input"))
      (node (ref "LED14") (pin "3") (pinfunction "VDD_3") (pintype "unspecified"))
      (node (ref "R14") (pin "1") (pinfunction "1_1") (pintype "unspecified"))
    )
    (net (code "31") (name "Net-(LED15-DOUT)") (class "Default")
      (node (ref "LED15") (pin "2") (pinfunction "DOUT_2") (pintype "unspecified"))
      (node (ref "LED16") (pin "4") (pinfunction "DIN_4") (pintype "unspecified"))
    )
    (net (code "32") (name "Net-(LED15-VDD)") (class "Default")
      (node (ref "C15") (pin "1") (pinfunction "1_1") (pintype "input"))
      (node (ref "LED15") (pin "3") (pinfunction "VDD_3") (pintype "unspecified"))
      (node (ref "R15") (pin "1") (pinfunction "1_1") (pintype "unspecified"))
    )
    (net (code "33") (name "Net-(LED16-VDD)") (class "Default")
      (node (ref "C16") (pin "1") (pinfunction "1_1") (pintype "input"))
      (node (ref "LED16") (pin "3") (pinfunction "VDD_3") (pintype "unspecified"))
      (node (ref "R16") (pin "1") (pinfunction "1_1") (pintype "unspecified"))
    )
    (net (code "34") (name "Net-(LED17-DIN)") (class "Default")
      (node (ref "LED17") (pin "4") (pinfunction "DIN_4") (pintype "unspecified"))
      (node (ref "U1") (pin "6") (pinfunction "D3_6") (pintype "unspecified"))
    )
    (net (code "35") (name "Net-(LED17-DOUT)") (class "Default")
      (node (ref "LED17") (pin "2") (pinfunction "DOUT_2") (pintype "unspecified"))
      (node (ref "LED18") (pin "4") (pinfunction "DIN_4") (pintype "unspecified"))
    )
    (net (code "36") (name "Net-(LED17-VDD)") (class "Default")
      (node (ref "C17") (pin "1") (pinfunction "1_1") (pintype "input"))
      (node (ref "LED17") (pin "3") (pinfunction "VDD_3") (pintype "unspecified"))
      (node (ref "R17") (pin "1") (pinfunction "1_1") (pintype "unspecified"))
    )
    (net (code "37") (name "Net-(LED18-DOUT)") (class "Default")
      (node (ref "LED18") (pin "2") (pinfunction "DOUT_2") (pintype "unspecified"))
      (node (ref "LED19") (pin "4") (pinfunction "DIN_4") (pintype "unspecified"))
    )
    (net (code "38") (name "Net-(LED18-VDD)") (class "Default")
      (node (ref "C18") (pin "1") (pinfunction "1_1") (pintype "input"))
      (node (ref "LED18") (pin "3") (pinfunction "VDD_3") (pintype "unspecified"))
      (node (ref "R18") (pin "1") (pinfunction "1_1") (pintype "unspecified"))
    )
    (net (code "39") (name "Net-(LED19-DOUT)") (class "Default")
      (node (ref "LED19") (pin "2") (pinfunction "DOUT_2") (pintype "unspecified"))
      (node (ref "LED20") (pin "4") (pinfunction "DIN_4") (pintype "unspecified"))
    )
    (net (code "40") (name "Net-(LED19-VDD)") (class "Default")
      (node (ref "C19") (pin "1") (pinfunction "1_1") (pintype "input"))
      (node (ref "LED19") (pin "3") (pinfunction "VDD_3") (pintype "unspecified"))
      (node (ref "R19") (pin "1") (pinfunction "1_1") (pintype "unspecified"))
    )
    (net (code "41") (name "Net-(LED20-DOUT)") (class "Default")
      (node (ref "LED20") (pin "2") (pinfunction "DOUT_2") (pintype "unspecified"))
      (node (ref "LED21") (pin "4") (pinfunction "DIN_4") (pintype "unspecified"))
    )
    (net (code "42") (name "Net-(LED20-VDD)") (class "Default")
      (node (ref "C20") (pin "1") (pinfunction "1_1") (pintype "input"))
      (node (ref "LED20") (pin "3") (pinfunction "VDD_3") (pintype "unspecified"))
      (node (ref "R20") (pin "1") (pinfunction "1_1") (pintype "unspecified"))
    )
    (net (code "43") (name "Net-(LED21-DOUT)") (class "Default")
      (node (ref "LED21") (pin "2") (pinfunction "DOUT_2") (pintype "unspecified"))
      (node (ref "LED22") (pin "4") (pinfunction "DIN_4") (pintype "unspecified"))
    )
    (net (code "44") (name "Net-(LED21-VDD)") (class "Default")
      (node (ref "C21") (pin "1") (pinfunction "1_1") (pintype "input"))
      (node (ref "LED21") (pin "3") (pinfunction "VDD_3") (pintype "unspecified"))
      (node (ref "R21") (pin "1") (pinfunction "1_1") (pintype "unspecified"))
    )
    (net (code "45") (name "Net-(LED22-DOUT)") (class "Default")
      (node (ref "LED22") (pin "2") (pinfunction "DOUT_2") (pintype "unspecified"))
      (node (ref "LED23") (pin "4") (pinfunction "DIN_4") (pintype "unspecified"))
    )
    (net (code "46") (name "Net-(LED22-VDD)") (class "Default")
      (node (ref "C22") (pin "1") (pinfunction "1_1") (pintype "input"))
      (node (ref "LED22") (pin "3") (pinfunction "VDD_3") (pintype "unspecified"))
      (node (ref "R22") (pin "1") (pinfunction "1_1") (pintype "unspecified"))
    )
    (net (code "47") (name "Net-(LED23-DOUT)") (class "Default")
      (node (ref "LED23") (pin "2") (pinfunction "DOUT_2") (pintype "unspecified"))
      (node (ref "LED24") (pin "4") (pinfunction "DIN_4") (pintype "unspecified"))
    )
    (net (code "48") (name "Net-(LED23-VDD)") (class "Default")
      (node (ref "C23") (pin "1") (pinfunction "1_1") (pintype "input"))
      (node (ref "LED23") (pin "3") (pinfunction "VDD_3") (pintype "unspecified"))
      (node (ref "R23") (pin "1") (pinfunction "1_1") (pintype "unspecified"))
    )
    (net (code "49") (name "Net-(LED24-DOUT)") (class "Default")
      (node (ref "LED24") (pin "2") (pinfunction "DOUT_2") (pintype "unspecified"))
      (node (ref "LED25") (pin "4") (pinfunction "DIN_4") (pintype "unspecified"))
    )
    (net (code "50") (name "Net-(LED24-VDD)") (class "Default")
      (node (ref "C24") (pin "1") (pinfunction "1_1") (pintype "input"))
      (node (ref "LED24") (pin "3") (pinfunction "VDD_3") (pintype "unspecified"))
      (node (ref "R24") (pin "1") (pinfunction "1_1") (pintype "unspecified"))
    )
    (net (code "51") (name "Net-(LED25-DOUT)") (class "Default")
      (node (ref "LED25") (pin "2") (pinfunction "DOUT_2") (pintype "unspecified"))
      (node (ref "LED26") (pin "4") (pinfunction "DIN_4") (pintype "unspecified"))
    )
    (net (code "52") (name "Net-(LED25-VDD)") (class "Default")
      (node (ref "C25") (pin "1") (pinfunction "1_1") (pintype "input"))
      (node (ref "LED25") (pin "3") (pinfunction "VDD_3") (pintype "unspecified"))
      (node (ref "R25") (pin "1") (pinfunction "1_1") (pintype "unspecified"))
    )
    (net (code "53") (name "Net-(LED26-DOUT)") (class "Default")
      (node (ref "LED26") (pin "2") (pinfunction "DOUT_2") (pintype "unspecified"))
      (node (ref "LED27") (pin "4") (pinfunction "DIN_4") (pintype "unspecified"))
    )
    (net (code "54") (name "Net-(LED26-VDD)") (class "Default")
      (node (ref "C26") (pin "1") (pinfunction "1_1") (pintype "input"))
      (node (ref "LED26") (pin "3") (pinfunction "VDD_3") (pintype "unspecified"))
      (node (ref "R26") (pin "1") (pinfunction "1_1") (pintype "unspecified"))
    )
    (net (code "55") (name "Net-(LED27-DOUT)") (class "Default")
      (node (ref "LED27") (pin "2") (pinfunction "DOUT_2") (pintype "unspecified"))
      (node (ref "LED28") (pin "4") (pinfunction "DIN_4") (pintype "unspecified"))
    )
    (net (code "56") (name "Net-(LED27-VDD)") (class "Default")
      (node (ref "C27") (pin "1") (pinfunction "1_1") (pintype "input"))
      (node (ref "LED27") (pin "3") (pinfunction "VDD_3") (pintype "unspecified"))
      (node (ref "R27") (pin "1") (pinfunction "1_1") (pintype "unspecified"))
    )
    (net (code "57") (name "Net-(LED28-DOUT)") (class "Default")
      (node (ref "LED28") (pin "2") (pinfunction "DOUT_2") (pintype "unspecified"))
      (node (ref "LED29") (pin "4") (pinfunction "DIN_4") (pintype "unspecified"))
    )
    (net (code "58") (name "Net-(LED28-VDD)") (class "Default")
      (node (ref "C28") (pin "1") (pinfunction "1_1") (pintype "input"))
      (node (ref "LED28") (pin "3") (pinfunction "VDD_3") (pintype "unspecified"))
      (node (ref "R28") (pin "1") (pinfunction "1_1") (pintype "unspecified"))
    )
    (net (code "59") (name "Net-(LED29-DOUT)") (class "Default")
      (node (ref "LED29") (pin "2") (pinfunction "DOUT_2") (pintype "unspecified"))
      (node (ref "LED30") (pin "4") (pinfunction "DIN_4") (pintype "unspecified"))
    )
    (net (code "60") (name "Net-(LED29-VDD)") (class "Default")
      (node (ref "C29") (pin "1") (pinfunction "1_1") (pintype "input"))
      (node (ref "LED29") (pin "3") (pinfunction "VDD_3") (pintype "unspecified"))
      (node (ref "R29") (pin "1") (pinfunction "1_1") (pintype "unspecified"))
    )
    (net (code "61") (name "Net-(LED30-DOUT)") (class "Default")
      (node (ref "LED30") (pin "2") (pinfunction "DOUT_2") (pintype "unspecified"))
      (node (ref "LED31") (pin "4") (pinfunction "DIN_4") (pintype "unspecified"))
    )
    (net (code "62") (name "Net-(LED30-VDD)") (class "Default")
      (node (ref "C30") (pin "1") (pinfunction "1_1") (pintype "input"))
      (node (ref "LED30") (pin "3") (pinfunction "VDD_3") (pintype "unspecified"))
      (node (ref "R30") (pin "1") (pinfunction "1_1") (pintype "unspecified"))
    )
    (net (code "63") (name "Net-(LED31-DOUT)") (class "Default")
      (node (ref "LED31") (pin "2") (pinfunction "DOUT_2") (pintype "unspecified"))
      (node (ref "LED32") (pin "4") (pinfunction "DIN_4") (pintype "unspecified"))
    )
    (net (code "64") (name "Net-(LED31-VDD)") (class "Default")
      (node (ref "C31") (pin "1") (pinfunction "1_1") (pintype "input"))
      (node (ref "LED31") (pin "3") (pinfunction "VDD_3") (pintype "unspecified"))
      (node (ref "R31") (pin "1") (pinfunction "1_1") (pintype "unspecified"))
    )
    (net (code "65") (name "Net-(LED32-VDD)") (class "Default")
      (node (ref "C32") (pin "1") (pinfunction "1_1") (pintype "input"))
      (node (ref "LED32") (pin "3") (pinfunction "VDD_3") (pintype "unspecified"))
      (node (ref "R32") (pin "1") (pinfunction "1_1") (pintype "unspecified"))
    )
    (net (code "66") (name "Net-(R_B-Pad1)") (class "Default")
      (node (ref "R_B") (pin "1") (pinfunction "1_1") (pintype "input"))
      (node (ref "R_G") (pin "1") (pinfunction "1_1") (pintype "input"))
      (node (ref "R_H") (pin "1") (pinfunction "1_1") (pintype "input"))
      (node (ref "R_R") (pin "1") (pinfunction "1_1") (pintype "input"))
      (node (ref "R_S") (pin "1") (pinfunction "1_1") (pintype "input"))
      (node (ref "R_V") (pin "1") (pinfunction "1_1") (pintype "input"))
      (node (ref "U1") (pin "29") (pinfunction "GND_29") (pintype "unspecified"))
    )
    (net (code "67") (name "Net-(SW1-Pad2)") (class "Default")
      (node (ref "SW1") (pin "2") (pinfunction "2_2") (pintype "unspecified"))
      (node (ref "VCC") (pin "1") (pinfunction "1_1") (pintype "unspecified"))
    )
    (net (code "68") (name "Net-(U1-5V)") (class "Default")
      (node (ref "R_B") (pin "3") (pinfunction "3_3") (pintype "input"))
      (node (ref "R_G") (pin "3") (pinfunction "3_3") (pintype "input"))
      (node (ref "R_H") (pin "3") (pinfunction "3_3") (pintype "input"))
      (node (ref "R_R") (pin "3") (pinfunction "3_3") (pintype "input"))
      (node (ref "R_S") (pin "3") (pinfunction "3_3") (pintype "input"))
      (node (ref "R_V") (pin "3") (pinfunction "3_3") (pintype "input"))
      (node (ref "U1") (pin "27") (pinfunction "5V_27") (pintype "unspecified"))
    )
    (net (code "69") (name "Net-(U1-A0)") (class "Default")
      (node (ref "R_H") (pin "2") (pinfunction "2_2") (pintype "input"))
      (node (ref "U1") (pin "19") (pinfunction "A0_19") (pintype "unspecified"))
    )
    (net (code "70") (name "Net-(U1-A1)") (class "Default")
      (node (ref "R_S") (pin "2") (pinfunction "2_2") (pintype "input"))
      (node (ref "U1") (pin "20") (pinfunction "A1_20") (pintype "unspecified"))
    )
    (net (code "71") (name "Net-(U1-A2)") (class "Default")
      (node (ref "R_V") (pin "2") (pinfunction "2_2") (pintype "input"))
      (node (ref "U1") (pin "21") (pinfunction "A2_21") (pintype "unspecified"))
    )
    (net (code "72") (name "Net-(U1-A3)") (class "Default")
      (node (ref "R_R") (pin "2") (pinfunction "2_2") (pintype "input"))
      (node (ref "U1") (pin "22") (pinfunction "A3_22") (pintype "unspecified"))
    )
    (net (code "73") (name "Net-(U1-A4)") (class "Default")
      (node (ref "R_G") (pin "2") (pinfunction "2_2") (pintype "input"))
      (node (ref "U1") (pin "23") (pinfunction "A4_23") (pintype "unspecified"))
    )
    (net (code "74") (name "Net-(U1-A5)") (class "Default")
      (node (ref "R_B") (pin "2") (pinfunction "2_2") (pintype "input"))
      (node (ref "U1") (pin "24") (pinfunction "A5_24") (pintype "unspecified"))
    )
    (net (code "75") (name "Net-(U1-Vin)") (class "Default")
      (node (ref "R1") (pin "2") (pinfunction "2_2") (pintype "unspecified"))
      (node (ref "R10") (pin "2") (pinfunction "2_2") (pintype "unspecified"))
      (node (ref "R11") (pin "2") (pinfunction "2_2") (pintype "unspecified"))
      (node (ref "R12") (pin "2") (pinfunction "2_2") (pintype "unspecified"))
      (node (ref "R13") (pin "2") (pinfunction "2_2") (pintype "unspecified"))
      (node (ref "R14") (pin "2") (pinfunction "2_2") (pintype "unspecified"))
      (node (ref "R15") (pin "2") (pinfunction "2_2") (pintype "unspecified"))
      (node (ref "R16") (pin "2") (pinfunction "2_2") (pintype "unspecified"))
      (node (ref "R17") (pin "2") (pinfunction "2_2") (pintype "unspecified"))
      (node (ref "R18") (pin "2") (pinfunction "2_2") (pintype "unspecified"))
      (node (ref "R19") (pin "2") (pinfunction "2_2") (pintype "unspecified"))
      (node (ref "R2") (pin "2") (pinfunction "2_2") (pintype "unspecified"))
      (node (ref "R20") (pin "2") (pinfunction "2_2") (pintype "unspecified"))
      (node (ref "R21") (pin "2") (pinfunction "2_2") (pintype "unspecified"))
      (node (ref "R22") (pin "2") (pinfunction "2_2") (pintype "unspecified"))
      (node (ref "R23") (pin "2") (pinfunction "2_2") (pintype "unspecified"))
      (node (ref "R24") (pin "2") (pinfunction "2_2") (pintype "unspecified"))
      (node (ref "R25") (pin "2") (pinfunction "2_2") (pintype "unspecified"))
      (node (ref "R26") (pin "2") (pinfunction "2_2") (pintype "unspecified"))
      (node (ref "R27") (pin "2") (pinfunction "2_2") (pintype "unspecified"))
      (node (ref "R28") (pin "2") (pinfunction "2_2") (pintype "unspecified"))
      (node (ref "R29") (pin "2") (pinfunction "2_2") (pintype "unspecified"))
      (node (ref "R3") (pin "2") (pinfunction "2_2") (pintype "unspecified"))
      (node (ref "R30") (pin "2") (pinfunction "2_2") (pintype "unspecified"))
      (node (ref "R31") (pin "2") (pinfunction "2_2") (pintype "unspecified"))
      (node (ref "R32") (pin "2") (pinfunction "2_2") (pintype "unspecified"))
      (node (ref "R4") (pin "2") (pinfunction "2_2") (pintype "unspecified"))
      (node (ref "R5") (pin "2") (pinfunction "2_2") (pintype "unspecified"))
      (node (ref "R6") (pin "2") (pinfunction "2_2") (pintype "unspecified"))
      (node (ref "R7") (pin "2") (pinfunction "2_2") (pintype "unspecified"))
      (node (ref "R8") (pin "2") (pinfunction "2_2") (pintype "unspecified"))
      (node (ref "R9") (pin "2") (pinfunction "2_2") (pintype "unspecified"))
      (node (ref "SW1") (pin "1") (pinfunction "1_1") (pintype "unspecified"))
      (node (ref "U1") (pin "30") (pinfunction "Vin_30") (pintype "unspecified"))
    )
    (net (code "76") (name "unconnected-(LED16-DOUT-Pad2)") (class "Default")
      (node (ref "LED16") (pin "2") (pinfunction "DOUT_2") (pintype "unspecified"))
    )
    (net (code "77") (name "unconnected-(LED32-DOUT-Pad2)") (class "Default")
      (node (ref "LED32") (pin "2") (pinfunction "DOUT_2") (pintype "unspecified"))
    )
    (net (code "78") (name "unconnected-(U1-3V3-Pad17)") (class "Default")
      (node (ref "U1") (pin "17") (pinfunction "3V3_17") (pintype "unspecified"))
    )
    (net (code "79") (name "unconnected-(U1-A6-Pad25)") (class "Default")
      (node (ref "U1") (pin "25") (pinfunction "A6_25") (pintype "unspecified"))
    )
    (net (code "80") (name "unconnected-(U1-A7-Pad26)") (class "Default")
      (node (ref "U1") (pin "26") (pinfunction "A7_26") (pintype "unspecified"))
    )
    (net (code "81") (name "unconnected-(U1-D4-Pad7)") (class "Default")
      (node (ref "U1") (pin "7") (pinfunction "D4_7") (pintype "unspecified"))
    )
    (net (code "82") (name "unconnected-(U1-D5-Pad8)") (class "Default")
      (node (ref "U1") (pin "8") (pinfunction "D5_8") (pintype "unspecified"))
    )
    (net (code "83") (name "unconnected-(U1-D6-Pad9)") (class "Default")
      (node (ref "U1") (pin "9") (pinfunction "D6_9") (pintype "unspecified"))
    )
    (net (code "84") (name "unconnected-(U1-D7-Pad10)") (class "Default")
      (node (ref "U1") (pin "10") (pinfunction "D7_10") (pintype "unspecified"))
    )
    (net (code "85") (name "unconnected-(U1-D8-Pad11)") (class "Default")
      (node (ref "U1") (pin "11") (pinfunction "D8_11") (pintype "unspecified"))
    )
    (net (code "86") (name "unconnected-(U1-D9-Pad12)") (class "Default")
      (node (ref "U1") (pin "12") (pinfunction "D9_12") (pintype "unspecified"))
    )
    (net (code "87") (name "unconnected-(U1-D10-Pad13)") (class "Default")
      (node (ref "U1") (pin "13") (pinfunction "D10_13") (pintype "unspecified"))
    )
    (net (code "88") (name "unconnected-(U1-D11-Pad14)") (class "Default")
      (node (ref "U1") (pin "14") (pinfunction "D11_14") (pintype "unspecified"))
    )
    (net (code "89") (name "unconnected-(U1-D12-Pad15)") (class "Default")
      (node (ref "U1") (pin "15") (pinfunction "D12_15") (pintype "unspecified"))
    )
    (net (code "90") (name "unconnected-(U1-D13-Pad16)") (class "Default")
      (node (ref "U1") (pin "16") (pinfunction "D13_16") (pintype "unspecified"))
    )
    (net (code "91") (name "unconnected-(U1-REF-Pad18)") (class "Default")
      (node (ref "U1") (pin "18") (pinfunction "REF_18") (pintype "unspecified"))
    )
    (net (code "92") (name "unconnected-(U1-RST-Pad3)") (class "Default")
      (node (ref "U1") (pin "3") (pinfunction "RST_3") (pintype "unspecified"))
    )
    (net (code "93") (name "unconnected-(U1-RST-Pad28)") (class "Default")
      (node (ref "U1") (pin "28") (pinfunction "RST_28") (pintype "unspecified"))
    )
    (net (code "94") (name "unconnected-(U1-RXD-Pad2)") (class "Default")
      (node (ref "U1") (pin "2") (pinfunction "RXD_2") (pintype "unspecified"))
    )
    (net (code "95") (name "unconnected-(U1-TXD-Pad1)") (class "Default")
      (node (ref "U1") (pin "1") (pinfunction "TXD_1") (pintype "unspecified"))
    )
  )
)
